# ZYNQ-PS.net
KiCad netlist of a schematic drawn in Altium Designer
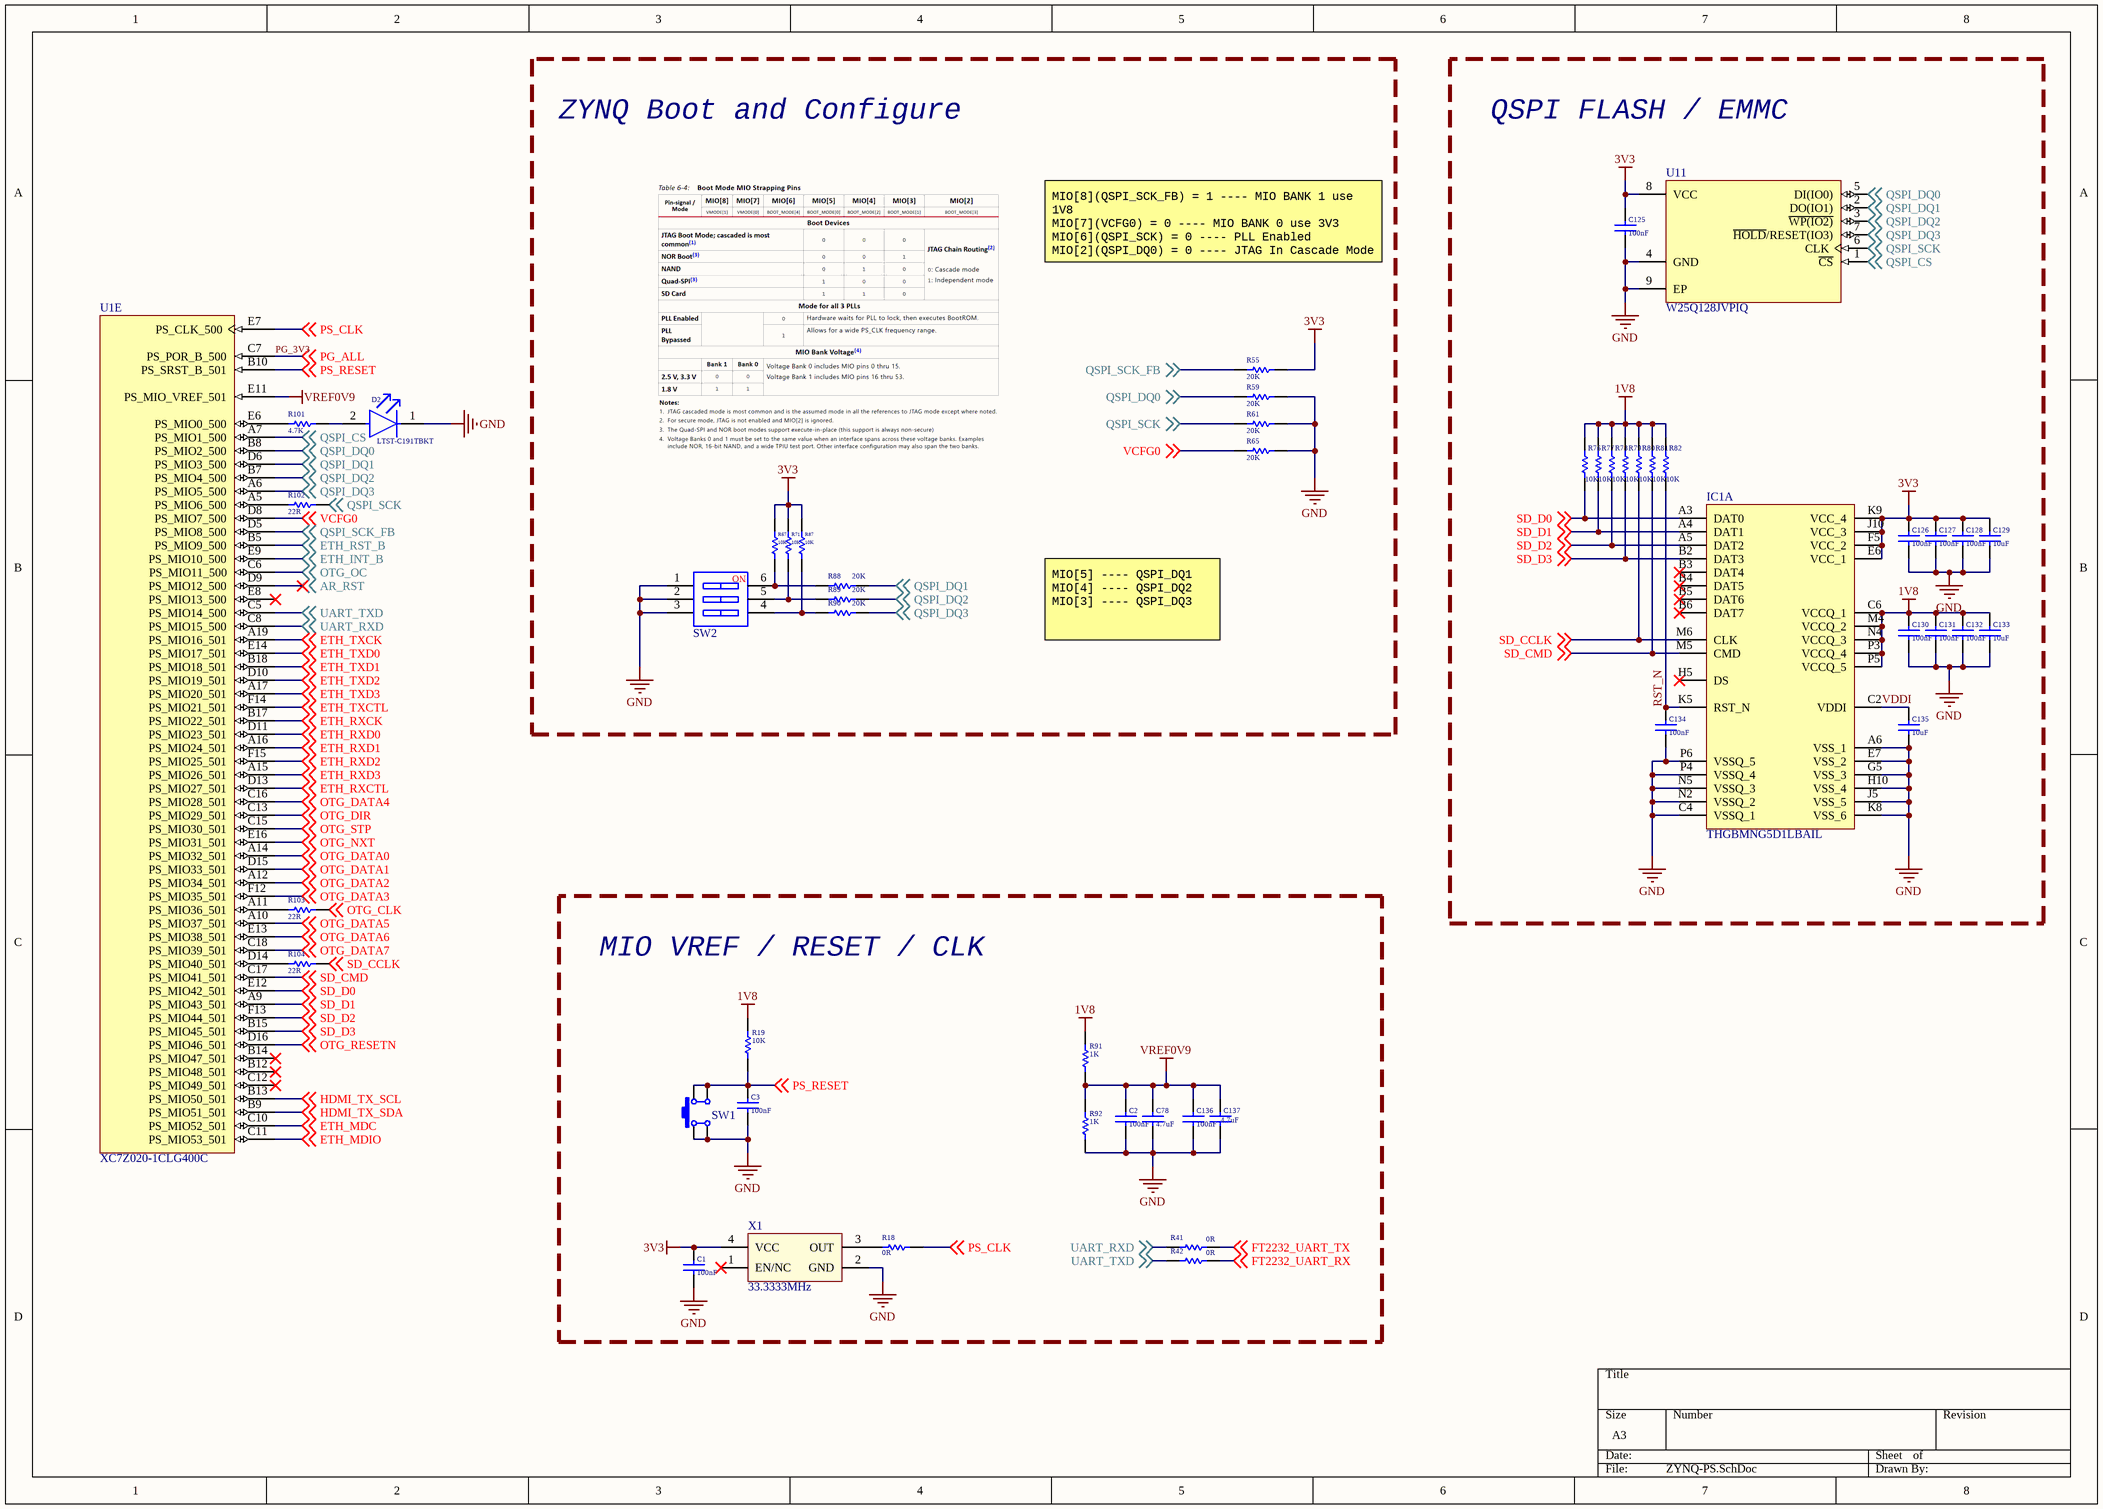
[diagram p0: ZYNQ-PS.SchDoc]

(export (version "E")
  (design (tool "Eeschema 10.0.6"))
  (components
    (comp (ref "C1")
      (value "100nF")
      (footprint "CAPC1005X55X25LL05T10")
      (fields (field (name "PART NUMBER") "GRM155R71H104KE14D") (field (name "MANUFACTURER") "Murata"))
      (libsource (lib "Altium Content Vault") (part "CAP"))
    )
    (comp (ref "C2")
      (value "100nF")
      (footprint "CAPC1005X55X25LL05T10")
      (fields (field (name "PART NUMBER") "GRM155R71H104KE14D") (field (name "MANUFACTURER") "Murata"))
      (libsource (lib "Altium Content Vault") (part "CAP"))
    )
    (comp (ref "C3")
      (value "100nF")
      (footprint "CAPC1005X55X25LL05T10")
      (fields (field (name "PART NUMBER") "GRM155R71H104KE14D") (field (name "MANUFACTURER") "Murata"))
      (libsource (lib "Altium Content Vault") (part "CAP"))
    )
    (comp (ref "C78")
      (value "4.7uF")
      (footprint "CAPC1005X55X25LL05T10")
      (fields (field (name "PART NUMBER") "GRM155R71H104KE14D") (field (name "MANUFACTURER") "Murata"))
      (libsource (lib "Altium Content Vault") (part "CAP"))
    )
    (comp (ref "C125")
      (value "100nF")
      (footprint "CAPC1005X55X25LL05T10")
      (fields (field (name "PART NUMBER") "GRM155R71H104KE14D") (field (name "MANUFACTURER") "Murata"))
      (libsource (lib "Altium Content Vault") (part "CAP"))
    )
    (comp (ref "C126")
      (value "100nF")
      (footprint "CAPC1005X55X25LL05T10")
      (fields (field (name "PART NUMBER") "GRM155R71H104KE14D") (field (name "MANUFACTURER") "Murata"))
      (libsource (lib "Altium Content Vault") (part "CAP"))
    )
    (comp (ref "C127")
      (value "100nF")
      (footprint "CAPC1005X55X25LL05T10")
      (fields (field (name "PART NUMBER") "GRM155R71H104KE14D") (field (name "MANUFACTURER") "Murata"))
      (libsource (lib "Altium Content Vault") (part "CAP"))
    )
    (comp (ref "C128")
      (value "100nF")
      (footprint "CAPC1005X55X25LL05T10")
      (fields (field (name "PART NUMBER") "GRM155R71H104KE14D") (field (name "MANUFACTURER") "Murata"))
      (libsource (lib "Altium Content Vault") (part "CAP"))
    )
    (comp (ref "C129")
      (value "10uF")
      (footprint "CAPC1005X55X25LL05T10")
      (fields (field (name "PART NUMBER") "GRM155R71H104KE14D") (field (name "MANUFACTURER") "Murata"))
      (libsource (lib "Altium Content Vault") (part "CAP"))
    )
    (comp (ref "C130")
      (value "100nF")
      (footprint "CAPC1005X55X25LL05T10")
      (fields (field (name "PART NUMBER") "GRM155R71H104KE14D") (field (name "MANUFACTURER") "Murata"))
      (libsource (lib "Altium Content Vault") (part "CAP"))
    )
    (comp (ref "C131")
      (value "100nF")
      (footprint "CAPC1005X55X25LL05T10")
      (fields (field (name "PART NUMBER") "GRM155R71H104KE14D") (field (name "MANUFACTURER") "Murata"))
      (libsource (lib "Altium Content Vault") (part "CAP"))
    )
    (comp (ref "C132")
      (value "100nF")
      (footprint "CAPC1005X55X25LL05T10")
      (fields (field (name "PART NUMBER") "GRM155R71H104KE14D") (field (name "MANUFACTURER") "Murata"))
      (libsource (lib "Altium Content Vault") (part "CAP"))
    )
    (comp (ref "C133")
      (value "10uF")
      (footprint "CAPC1005X55X25LL05T10")
      (fields (field (name "PART NUMBER") "GRM155R71H104KE14D") (field (name "MANUFACTURER") "Murata"))
      (libsource (lib "Altium Content Vault") (part "CAP"))
    )
    (comp (ref "C134")
      (value "100nF")
      (footprint "CAPC1005X55X25LL05T10")
      (fields (field (name "PART NUMBER") "GRM155R71H104KE14D") (field (name "MANUFACTURER") "Murata"))
      (libsource (lib "Altium Content Vault") (part "CAP"))
    )
    (comp (ref "C135")
      (value "10uF")
      (footprint "CAPC1005X55X25LL05T10")
      (fields (field (name "PART NUMBER") "GRM155R71H104KE14D") (field (name "MANUFACTURER") "Murata"))
      (libsource (lib "Altium Content Vault") (part "CAP"))
    )
    (comp (ref "C136")
      (value "100nF")
      (footprint "CAPC1005X55X25LL05T10")
      (fields (field (name "PART NUMBER") "GRM155R71H104KE14D") (field (name "MANUFACTURER") "Murata"))
      (libsource (lib "Altium Content Vault") (part "CAP"))
    )
    (comp (ref "C137")
      (value "4.7uF")
      (footprint "CAPC1005X55X25LL05T10")
      (fields (field (name "PART NUMBER") "GRM155R71H104KE14D") (field (name "MANUFACTURER") "Murata"))
      (libsource (lib "Altium Content Vault") (part "CAP"))
    )
    (comp (ref "D2")
      (value "LTST-C191TBKT")
      (footprint "FP-LTST-C191TBKT-MFG")
      (description "LED BLUE CLEAR CHIP SMD")
      (libsource (lib "Altium Content Vault") (part "8706943c75ba83719d021d2fdc84c58"))
    )
    (comp (ref "IC1")
      (value "THGBMNG5D1LBAIL")
      (footprint "SamacSys:BGA153C50P14X14_1150X1300X80")
      (description "Integrated Circuit")
      (libsource (lib "SamacSys") (part "THGBMNG5D1LBAIL"))
    )
    (comp (ref "R18")
      (value "0R")
      (footprint "RESC1005X40X25LL05T05")
      (fields (field (name "MANUFACTURER") "Panasonic") (field (name "PART NUMBER") "ERJ-2RKF40R2X"))
      (libsource (lib "Altium Content Vault") (part "RES"))
    )
    (comp (ref "R19")
      (value "10K")
      (footprint "RESC1005X40X25LL05T05")
      (fields (field (name "MANUFACTURER") "Panasonic") (field (name "PART NUMBER") "ERJ-2RKF40R2X"))
      (libsource (lib "Altium Content Vault") (part "RES"))
    )
    (comp (ref "R41")
      (value "0R")
      (footprint "RESC1005X40X25LL05T05")
      (fields (field (name "MANUFACTURER") "Panasonic") (field (name "PART NUMBER") "ERJ-2RKF40R2X"))
      (libsource (lib "Altium Content Vault") (part "RES"))
    )
    (comp (ref "R42")
      (value "0R")
      (footprint "RESC1005X40X25LL05T05")
      (fields (field (name "MANUFACTURER") "Panasonic") (field (name "PART NUMBER") "ERJ-2RKF40R2X"))
      (libsource (lib "Altium Content Vault") (part "RES"))
    )
    (comp (ref "R55")
      (value "20K")
      (footprint "RESC1005X40X25LL05T05")
      (fields (field (name "MANUFACTURER") "Panasonic") (field (name "PART NUMBER") "ERJ-2RKF40R2X"))
      (libsource (lib "Altium Content Vault") (part "RES"))
    )
    (comp (ref "R59")
      (value "20K")
      (footprint "RESC1005X40X25LL05T05")
      (fields (field (name "MANUFACTURER") "Panasonic") (field (name "PART NUMBER") "ERJ-2RKF40R2X"))
      (libsource (lib "Altium Content Vault") (part "RES"))
    )
    (comp (ref "R61")
      (value "20K")
      (footprint "RESC1005X40X25LL05T05")
      (fields (field (name "MANUFACTURER") "Panasonic") (field (name "PART NUMBER") "ERJ-2RKF40R2X"))
      (libsource (lib "Altium Content Vault") (part "RES"))
    )
    (comp (ref "R65")
      (value "20K")
      (footprint "RESC1005X40X25LL05T05")
      (fields (field (name "MANUFACTURER") "Panasonic") (field (name "PART NUMBER") "ERJ-2RKF40R2X"))
      (libsource (lib "Altium Content Vault") (part "RES"))
    )
    (comp (ref "R67")
      (value "10K")
      (footprint "RESC1005X40X25LL05T05")
      (fields (field (name "MANUFACTURER") "Panasonic") (field (name "PART NUMBER") "ERJ-2RKF40R2X"))
      (libsource (lib "Altium Content Vault") (part "RES"))
    )
    (comp (ref "R71")
      (value "10K")
      (footprint "RESC1005X40X25LL05T05")
      (fields (field (name "MANUFACTURER") "Panasonic") (field (name "PART NUMBER") "ERJ-2RKF40R2X"))
      (libsource (lib "Altium Content Vault") (part "RES"))
    )
    (comp (ref "R76")
      (value "10K")
      (footprint "RESC1005X40X25LL05T05")
      (fields (field (name "MANUFACTURER") "Panasonic") (field (name "PART NUMBER") "ERJ-2RKF40R2X"))
      (libsource (lib "Altium Content Vault") (part "RES"))
    )
    (comp (ref "R77")
      (value "10K")
      (footprint "RESC1005X40X25LL05T05")
      (fields (field (name "MANUFACTURER") "Panasonic") (field (name "PART NUMBER") "ERJ-2RKF40R2X"))
      (libsource (lib "Altium Content Vault") (part "RES"))
    )
    (comp (ref "R78")
      (value "10K")
      (footprint "RESC1005X40X25LL05T05")
      (fields (field (name "MANUFACTURER") "Panasonic") (field (name "PART NUMBER") "ERJ-2RKF40R2X"))
      (libsource (lib "Altium Content Vault") (part "RES"))
    )
    (comp (ref "R79")
      (value "10K")
      (footprint "RESC1005X40X25LL05T05")
      (fields (field (name "MANUFACTURER") "Panasonic") (field (name "PART NUMBER") "ERJ-2RKF40R2X"))
      (libsource (lib "Altium Content Vault") (part "RES"))
    )
    (comp (ref "R80")
      (value "10K")
      (footprint "RESC1005X40X25LL05T05")
      (fields (field (name "MANUFACTURER") "Panasonic") (field (name "PART NUMBER") "ERJ-2RKF40R2X"))
      (libsource (lib "Altium Content Vault") (part "RES"))
    )
    (comp (ref "R81")
      (value "10K")
      (footprint "RESC1005X40X25LL05T05")
      (fields (field (name "MANUFACTURER") "Panasonic") (field (name "PART NUMBER") "ERJ-2RKF40R2X"))
      (libsource (lib "Altium Content Vault") (part "RES"))
    )
    (comp (ref "R82")
      (value "10K")
      (footprint "RESC1005X40X25LL05T05")
      (fields (field (name "MANUFACTURER") "Panasonic") (field (name "PART NUMBER") "ERJ-2RKF40R2X"))
      (libsource (lib "Altium Content Vault") (part "RES"))
    )
    (comp (ref "R87")
      (value "10K")
      (footprint "RESC1005X40X25LL05T05")
      (fields (field (name "MANUFACTURER") "Panasonic") (field (name "PART NUMBER") "ERJ-2RKF40R2X"))
      (libsource (lib "Altium Content Vault") (part "RES"))
    )
    (comp (ref "R88")
      (value "20K")
      (footprint "RESC1005X40X25LL05T05")
      (fields (field (name "MANUFACTURER") "Panasonic") (field (name "PART NUMBER") "ERJ-2RKF40R2X"))
      (libsource (lib "Altium Content Vault") (part "RES"))
    )
    (comp (ref "R89")
      (value "20K")
      (footprint "RESC1005X40X25LL05T05")
      (fields (field (name "MANUFACTURER") "Panasonic") (field (name "PART NUMBER") "ERJ-2RKF40R2X"))
      (libsource (lib "Altium Content Vault") (part "RES"))
    )
    (comp (ref "R90")
      (value "20K")
      (footprint "RESC1005X40X25LL05T05")
      (fields (field (name "MANUFACTURER") "Panasonic") (field (name "PART NUMBER") "ERJ-2RKF40R2X"))
      (libsource (lib "Altium Content Vault") (part "RES"))
    )
    (comp (ref "R91")
      (value "1K")
      (footprint "RESC1005X40X25LL05T05")
      (fields (field (name "MANUFACTURER") "Panasonic") (field (name "PART NUMBER") "ERJ-2RKF40R2X"))
      (libsource (lib "Altium Content Vault") (part "RES"))
    )
    (comp (ref "R92")
      (value "1K")
      (footprint "RESC1005X40X25LL05T05")
      (fields (field (name "MANUFACTURER") "Panasonic") (field (name "PART NUMBER") "ERJ-2RKF40R2X"))
      (libsource (lib "Altium Content Vault") (part "RES"))
    )
    (comp (ref "R101")
      (value "4.7K")
      (footprint "RESC1005X40X25LL05T05")
      (fields (field (name "MANUFACTURER") "Panasonic") (field (name "PART NUMBER") "ERJ-2RKF40R2X"))
      (libsource (lib "Altium Content Vault") (part "RES"))
    )
    (comp (ref "R102")
      (value "22R")
      (footprint "RESC1005X40X25LL05T05")
      (fields (field (name "MANUFACTURER") "Panasonic") (field (name "PART NUMBER") "ERJ-2RKF40R2X"))
      (libsource (lib "Altium Content Vault") (part "RES"))
    )
    (comp (ref "R103")
      (value "22R")
      (footprint "RESC1005X40X25LL05T05")
      (fields (field (name "MANUFACTURER") "Panasonic") (field (name "PART NUMBER") "ERJ-2RKF40R2X"))
      (libsource (lib "Altium Content Vault") (part "RES"))
    )
    (comp (ref "R104")
      (value "22R")
      (footprint "RESC1005X40X25LL05T05")
      (fields (field (name "MANUFACTURER") "Panasonic") (field (name "PART NUMBER") "ERJ-2RKF40R2X"))
      (libsource (lib "Altium Content Vault") (part "RES"))
    )
    (comp (ref "SW1")
      (value "3*4*2.5")
      (footprint "SW-SMD-4.2x3.2_4P")
      (description "贴片4脚轻触开关")
      (libsource (lib "0.5 - 按键_开关_蜂鸣器_电池_测试点_Mark点_铜柱") (part "SW SMD-3*4*2.5"))
    )
    (comp (ref "SW2")
      (value "DIP-SW-3P")
      (footprint "SW1.27 SMD-3P")
      (description "3路拨码开关")
      (libsource (lib "0.5 - 按键_开关_蜂鸣器_电池_测试点_Mark点_铜柱") (part "DIP-SW-3P"))
    )
    (comp (ref "U1")
      (value "XC7Z020-1CLG400C")
      (footprint "CLG400")
      (fields (field (name "GENERIC PART NUMBER") "XC7Z020"))
      (libsource (lib "Altium Content Vault") (part "XNLX-XC7Z020-CLG400"))
    )
    (comp (ref "U11")
      (value "W25Q128JVPIQ")
      (footprint "FP-ZP-IPC_C")
      (libsource (lib "HainanU-RoboMaster-硬件组") (part "W25Q128JVPIQ"))
    )
    (comp (ref "X1")
      (value "33.3333MHz")
      (footprint "OSC-2025-4P")
      (description "4脚有源晶振(振荡器)")
      (libsource (lib "0.1 - 电阻-电容-电感-保险丝-晶振-晶体-磁珠-电位器-法拉电容-馈通电容") (part "XTAL-ACT-4P"))
    )
  )
  (nets
    (net (code "1") (name "/RST_N") (class "Default")
      (node (ref "C134") (pin "2") (pinfunction "2_2") (pintype "passive"))
      (node (ref "IC1") (pin "K5") (pinfunction "RST_N_K5") (pintype "passive"))
      (node (ref "R82") (pin "1") (pinfunction "1_1") (pintype "passive"))
    )
    (net (code "2") (name "/VDDI") (class "Default")
      (node (ref "C135") (pin "2") (pinfunction "2_2") (pintype "passive"))
      (node (ref "IC1") (pin "C2") (pinfunction "VDDI_C2") (pintype "passive"))
    )
    (net (code "3") (name "1V8") (class "Default")
      (node (ref "C130") (pin "2") (pinfunction "2_2") (pintype "passive"))
      (node (ref "C131") (pin "2") (pinfunction "2_2") (pintype "passive"))
      (node (ref "C132") (pin "2") (pinfunction "2_2") (pintype "passive"))
      (node (ref "C133") (pin "2") (pinfunction "2_2") (pintype "passive"))
      (node (ref "IC1") (pin "C6") (pinfunction "VCCQ_1_C6") (pintype "passive"))
      (node (ref "IC1") (pin "M4") (pinfunction "VCCQ_2_M4") (pintype "passive"))
      (node (ref "IC1") (pin "N4") (pinfunction "VCCQ_3_N4") (pintype "passive"))
      (node (ref "IC1") (pin "P3") (pinfunction "VCCQ_4_P3") (pintype "passive"))
      (node (ref "IC1") (pin "P5") (pinfunction "VCCQ_5_P5") (pintype "passive"))
      (node (ref "R19") (pin "2") (pinfunction "2_2") (pintype "passive"))
      (node (ref "R76") (pin "2") (pinfunction "2_2") (pintype "passive"))
      (node (ref "R77") (pin "2") (pinfunction "2_2") (pintype "passive"))
      (node (ref "R78") (pin "2") (pinfunction "2_2") (pintype "passive"))
      (node (ref "R79") (pin "2") (pinfunction "2_2") (pintype "passive"))
      (node (ref "R80") (pin "2") (pinfunction "2_2") (pintype "passive"))
      (node (ref "R81") (pin "2") (pinfunction "2_2") (pintype "passive"))
      (node (ref "R82") (pin "2") (pinfunction "2_2") (pintype "passive"))
      (node (ref "R91") (pin "2") (pinfunction "2_2") (pintype "passive"))
    )
    (net (code "4") (name "3V3") (class "Default")
      (node (ref "C1") (pin "2") (pinfunction "2_2") (pintype "passive"))
      (node (ref "C125") (pin "2") (pinfunction "2_2") (pintype "passive"))
      (node (ref "C126") (pin "2") (pinfunction "2_2") (pintype "passive"))
      (node (ref "C127") (pin "2") (pinfunction "2_2") (pintype "passive"))
      (node (ref "C128") (pin "2") (pinfunction "2_2") (pintype "passive"))
      (node (ref "C129") (pin "2") (pinfunction "2_2") (pintype "passive"))
      (node (ref "IC1") (pin "E6") (pinfunction "VCC_1_E6") (pintype "passive"))
      (node (ref "IC1") (pin "F5") (pinfunction "VCC_2_F5") (pintype "passive"))
      (node (ref "IC1") (pin "J10") (pinfunction "VCC_3_J10") (pintype "passive"))
      (node (ref "IC1") (pin "K9") (pinfunction "VCC_4_K9") (pintype "passive"))
      (node (ref "R55") (pin "1") (pinfunction "1_1") (pintype "passive"))
      (node (ref "R67") (pin "1") (pinfunction "1_1") (pintype "passive"))
      (node (ref "R71") (pin "1") (pinfunction "1_1") (pintype "passive"))
      (node (ref "R87") (pin "1") (pinfunction "1_1") (pintype "passive"))
      (node (ref "U11") (pin "8") (pinfunction "VCC_8") (pintype "power_in"))
      (node (ref "X1") (pin "4") (pinfunction "VCC_4") (pintype "passive"))
    )
    (net (code "5") (name "AR_RST") (class "Default")
      (node (ref "U1") (pin "D9") (pinfunction "PS_MIO12_500_D9") (pintype "bidirectional"))
    )
    (net (code "6") (name "ETH_INT_B") (class "Default")
      (node (ref "U1") (pin "E9") (pinfunction "PS_MIO10_500_E9") (pintype "bidirectional"))
    )
    (net (code "7") (name "ETH_MDC") (class "Default")
      (node (ref "U1") (pin "C10") (pinfunction "PS_MIO52_501_C10") (pintype "bidirectional"))
    )
    (net (code "8") (name "ETH_MDIO") (class "Default")
      (node (ref "U1") (pin "C11") (pinfunction "PS_MIO53_501_C11") (pintype "bidirectional"))
    )
    (net (code "9") (name "ETH_RST_B") (class "Default")
      (node (ref "U1") (pin "B5") (pinfunction "PS_MIO9_500_B5") (pintype "bidirectional"))
    )
    (net (code "10") (name "ETH_RXCK") (class "Default")
      (node (ref "U1") (pin "B17") (pinfunction "PS_MIO22_501_B17") (pintype "bidirectional"))
    )
    (net (code "11") (name "ETH_RXCTL") (class "Default")
      (node (ref "U1") (pin "D13") (pinfunction "PS_MIO27_501_D13") (pintype "bidirectional"))
    )
    (net (code "12") (name "ETH_RXD0") (class "Default")
      (node (ref "U1") (pin "D11") (pinfunction "PS_MIO23_501_D11") (pintype "bidirectional"))
    )
    (net (code "13") (name "ETH_RXD1") (class "Default")
      (node (ref "U1") (pin "A16") (pinfunction "PS_MIO24_501_A16") (pintype "bidirectional"))
    )
    (net (code "14") (name "ETH_RXD2") (class "Default")
      (node (ref "U1") (pin "F15") (pinfunction "PS_MIO25_501_F15") (pintype "bidirectional"))
    )
    (net (code "15") (name "ETH_RXD3") (class "Default")
      (node (ref "U1") (pin "A15") (pinfunction "PS_MIO26_501_A15") (pintype "bidirectional"))
    )
    (net (code "16") (name "ETH_TXCK") (class "Default")
      (node (ref "U1") (pin "A19") (pinfunction "PS_MIO16_501_A19") (pintype "bidirectional"))
    )
    (net (code "17") (name "ETH_TXCTL") (class "Default")
      (node (ref "U1") (pin "F14") (pinfunction "PS_MIO21_501_F14") (pintype "bidirectional"))
    )
    (net (code "18") (name "ETH_TXD0") (class "Default")
      (node (ref "U1") (pin "E14") (pinfunction "PS_MIO17_501_E14") (pintype "bidirectional"))
    )
    (net (code "19") (name "ETH_TXD1") (class "Default")
      (node (ref "U1") (pin "B18") (pinfunction "PS_MIO18_501_B18") (pintype "bidirectional"))
    )
    (net (code "20") (name "ETH_TXD2") (class "Default")
      (node (ref "U1") (pin "D10") (pinfunction "PS_MIO19_501_D10") (pintype "bidirectional"))
    )
    (net (code "21") (name "ETH_TXD3") (class "Default")
      (node (ref "U1") (pin "A17") (pinfunction "PS_MIO20_501_A17") (pintype "bidirectional"))
    )
    (net (code "22") (name "FT2232_UART_RX") (class "Default")
      (node (ref "R42") (pin "1") (pinfunction "1_1") (pintype "passive"))
    )
    (net (code "23") (name "FT2232_UART_TX") (class "Default")
      (node (ref "R41") (pin "1") (pinfunction "1_1") (pintype "passive"))
    )
    (net (code "24") (name "GND") (class "Default")
      (node (ref "C1") (pin "1") (pinfunction "1_1") (pintype "passive"))
      (node (ref "C125") (pin "1") (pinfunction "1_1") (pintype "passive"))
      (node (ref "C126") (pin "1") (pinfunction "1_1") (pintype "passive"))
      (node (ref "C127") (pin "1") (pinfunction "1_1") (pintype "passive"))
      (node (ref "C128") (pin "1") (pinfunction "1_1") (pintype "passive"))
      (node (ref "C129") (pin "1") (pinfunction "1_1") (pintype "passive"))
      (node (ref "C130") (pin "1") (pinfunction "1_1") (pintype "passive"))
      (node (ref "C131") (pin "1") (pinfunction "1_1") (pintype "passive"))
      (node (ref "C132") (pin "1") (pinfunction "1_1") (pintype "passive"))
      (node (ref "C133") (pin "1") (pinfunction "1_1") (pintype "passive"))
      (node (ref "C134") (pin "1") (pinfunction "1_1") (pintype "passive"))
      (node (ref "C135") (pin "1") (pinfunction "1_1") (pintype "passive"))
      (node (ref "C136") (pin "1") (pinfunction "1_1") (pintype "passive"))
      (node (ref "C137") (pin "1") (pinfunction "1_1") (pintype "passive"))
      (node (ref "C2") (pin "1") (pinfunction "1_1") (pintype "passive"))
      (node (ref "C3") (pin "1") (pinfunction "1_1") (pintype "passive"))
      (node (ref "C78") (pin "1") (pinfunction "1_1") (pintype "passive"))
      (node (ref "D2") (pin "1") (pinfunction "C_1") (pintype "passive"))
      (node (ref "IC1") (pin "A6") (pinfunction "VSS_1_A6") (pintype "passive"))
      (node (ref "IC1") (pin "C4") (pinfunction "VSSQ_1_C4") (pintype "passive"))
      (node (ref "IC1") (pin "E7") (pinfunction "VSS_2_E7") (pintype "passive"))
      (node (ref "IC1") (pin "G5") (pinfunction "VSS_3_G5") (pintype "passive"))
      (node (ref "IC1") (pin "H10") (pinfunction "VSS_4_H10") (pintype "passive"))
      (node (ref "IC1") (pin "J5") (pinfunction "VSS_5_J5") (pintype "passive"))
      (node (ref "IC1") (pin "K8") (pinfunction "VSS_6_K8") (pintype "passive"))
      (node (ref "IC1") (pin "N2") (pinfunction "VSSQ_2_N2") (pintype "passive"))
      (node (ref "IC1") (pin "N5") (pinfunction "VSSQ_3_N5") (pintype "passive"))
      (node (ref "IC1") (pin "P4") (pinfunction "VSSQ_4_P4") (pintype "passive"))
      (node (ref "IC1") (pin "P6") (pinfunction "VSSQ_5_P6") (pintype "passive"))
      (node (ref "R59") (pin "1") (pinfunction "1_1") (pintype "passive"))
      (node (ref "R61") (pin "1") (pinfunction "1_1") (pintype "passive"))
      (node (ref "R65") (pin "1") (pinfunction "1_1") (pintype "passive"))
      (node (ref "R92") (pin "1") (pinfunction "1_1") (pintype "passive"))
      (node (ref "SW1") (pin "1") (pinfunction "1_1") (pintype "passive"))
      (node (ref "SW1") (pin "4") (pinfunction "4_4") (pintype "passive"))
      (node (ref "SW2") (pin "1") (pinfunction "1_1") (pintype "passive"))
      (node (ref "SW2") (pin "2") (pinfunction "2_2") (pintype "passive"))
      (node (ref "SW2") (pin "3") (pinfunction "3_3") (pintype "passive"))
      (node (ref "U11") (pin "4") (pinfunction "GND_4") (pintype "power_in"))
      (node (ref "U11") (pin "9") (pinfunction "EP_9") (pintype "power_in"))
      (node (ref "X1") (pin "2") (pinfunction "GND_2") (pintype "passive"))
    )
    (net (code "25") (name "HDMI_TX_SCL") (class "Default")
      (node (ref "U1") (pin "B13") (pinfunction "PS_MIO50_501_B13") (pintype "bidirectional"))
    )
    (net (code "26") (name "HDMI_TX_SDA") (class "Default")
      (node (ref "U1") (pin "B9") (pinfunction "PS_MIO51_501_B9") (pintype "bidirectional"))
    )
    (net (code "27") (name "Net-(D2-A)") (class "Default")
      (node (ref "D2") (pin "2") (pinfunction "A_2") (pintype "passive"))
      (node (ref "R101") (pin "1") (pinfunction "1_1") (pintype "passive"))
    )
    (net (code "28") (name "Net-(R67-Pad2)") (class "Default")
      (node (ref "R67") (pin "2") (pinfunction "2_2") (pintype "passive"))
      (node (ref "R88") (pin "2") (pinfunction "2_2") (pintype "passive"))
      (node (ref "SW2") (pin "6") (pinfunction "6_6") (pintype "passive"))
    )
    (net (code "29") (name "Net-(R71-Pad2)") (class "Default")
      (node (ref "R71") (pin "2") (pinfunction "2_2") (pintype "passive"))
      (node (ref "R89") (pin "2") (pinfunction "2_2") (pintype "passive"))
      (node (ref "SW2") (pin "5") (pinfunction "5_5") (pintype "passive"))
    )
    (net (code "30") (name "Net-(R87-Pad2)") (class "Default")
      (node (ref "R87") (pin "2") (pinfunction "2_2") (pintype "passive"))
      (node (ref "R90") (pin "2") (pinfunction "2_2") (pintype "passive"))
      (node (ref "SW2") (pin "4") (pinfunction "4_4") (pintype "passive"))
    )
    (net (code "31") (name "Net-(U1E-PS_MIO0_500)") (class "Default")
      (node (ref "R101") (pin "2") (pinfunction "2_2") (pintype "passive"))
      (node (ref "U1") (pin "E6") (pinfunction "PS_MIO0_500_E6") (pintype "bidirectional"))
    )
    (net (code "32") (name "Net-(U1E-PS_MIO6_500)") (class "Default")
      (node (ref "R102") (pin "2") (pinfunction "2_2") (pintype "passive"))
      (node (ref "U1") (pin "A5") (pinfunction "PS_MIO6_500_A5") (pintype "bidirectional"))
    )
    (net (code "33") (name "Net-(U1E-PS_MIO36_501)") (class "Default")
      (node (ref "R103") (pin "2") (pinfunction "2_2") (pintype "passive"))
      (node (ref "U1") (pin "A11") (pinfunction "PS_MIO36_501_A11") (pintype "bidirectional"))
    )
    (net (code "34") (name "Net-(U1E-PS_MIO40_501)") (class "Default")
      (node (ref "R104") (pin "2") (pinfunction "2_2") (pintype "passive"))
      (node (ref "U1") (pin "D14") (pinfunction "PS_MIO40_501_D14") (pintype "bidirectional"))
    )
    (net (code "35") (name "Net-(X1-OUT)") (class "Default")
      (node (ref "R18") (pin "1") (pinfunction "1_1") (pintype "passive"))
      (node (ref "X1") (pin "3") (pinfunction "OUT_3") (pintype "passive"))
    )
    (net (code "36") (name "OTG_CLK") (class "Default")
      (node (ref "R103") (pin "1") (pinfunction "1_1") (pintype "passive"))
    )
    (net (code "37") (name "OTG_DATA0") (class "Default")
      (node (ref "U1") (pin "A14") (pinfunction "PS_MIO32_501_A14") (pintype "bidirectional"))
    )
    (net (code "38") (name "OTG_DATA1") (class "Default")
      (node (ref "U1") (pin "D15") (pinfunction "PS_MIO33_501_D15") (pintype "bidirectional"))
    )
    (net (code "39") (name "OTG_DATA2") (class "Default")
      (node (ref "U1") (pin "A12") (pinfunction "PS_MIO34_501_A12") (pintype "bidirectional"))
    )
    (net (code "40") (name "OTG_DATA3") (class "Default")
      (node (ref "U1") (pin "F12") (pinfunction "PS_MIO35_501_F12") (pintype "bidirectional"))
    )
    (net (code "41") (name "OTG_DATA4") (class "Default")
      (node (ref "U1") (pin "C16") (pinfunction "PS_MIO28_501_C16") (pintype "bidirectional"))
    )
    (net (code "42") (name "OTG_DATA5") (class "Default")
      (node (ref "U1") (pin "A10") (pinfunction "PS_MIO37_501_A10") (pintype "bidirectional"))
    )
    (net (code "43") (name "OTG_DATA6") (class "Default")
      (node (ref "U1") (pin "E13") (pinfunction "PS_MIO38_501_E13") (pintype "bidirectional"))
    )
    (net (code "44") (name "OTG_DATA7") (class "Default")
      (node (ref "U1") (pin "C18") (pinfunction "PS_MIO39_501_C18") (pintype "bidirectional"))
    )
    (net (code "45") (name "OTG_DIR") (class "Default")
      (node (ref "U1") (pin "C13") (pinfunction "PS_MIO29_501_C13") (pintype "bidirectional"))
    )
    (net (code "46") (name "OTG_NXT") (class "Default")
      (node (ref "U1") (pin "E16") (pinfunction "PS_MIO31_501_E16") (pintype "bidirectional"))
    )
    (net (code "47") (name "OTG_OC") (class "Default")
      (node (ref "U1") (pin "C6") (pinfunction "PS_MIO11_500_C6") (pintype "bidirectional"))
    )
    (net (code "48") (name "OTG_RESETN") (class "Default")
      (node (ref "U1") (pin "D16") (pinfunction "PS_MIO46_501_D16") (pintype "bidirectional"))
    )
    (net (code "49") (name "OTG_STP") (class "Default")
      (node (ref "U1") (pin "C15") (pinfunction "PS_MIO30_501_C15") (pintype "bidirectional"))
    )
    (net (code "50") (name "PG_ALL") (class "Default")
      (node (ref "U1") (pin "C7") (pinfunction "PS_POR_B_500_C7") (pintype "input"))
    )
    (net (code "51") (name "PS_CLK") (class "Default")
      (node (ref "R18") (pin "2") (pinfunction "2_2") (pintype "passive"))
      (node (ref "U1") (pin "E7") (pinfunction "PS_CLK_500_E7") (pintype "input"))
    )
    (net (code "52") (name "PS_RESET") (class "Default")
      (node (ref "C3") (pin "2") (pinfunction "2_2") (pintype "passive"))
      (node (ref "R19") (pin "1") (pinfunction "1_1") (pintype "passive"))
      (node (ref "SW1") (pin "2") (pinfunction "2_2") (pintype "passive"))
      (node (ref "SW1") (pin "3") (pinfunction "3_3") (pintype "passive"))
      (node (ref "U1") (pin "B10") (pinfunction "PS_SRST_B_501_B10") (pintype "input"))
    )
    (net (code "53") (name "QSPI_CS") (class "Default")
      (node (ref "U1") (pin "A7") (pinfunction "PS_MIO1_500_A7") (pintype "bidirectional"))
      (node (ref "U11") (pin "1") (pinfunction "~{CS}_1") (pintype "input"))
    )
    (net (code "54") (name "QSPI_DQ0") (class "Default")
      (node (ref "R59") (pin "2") (pinfunction "2_2") (pintype "passive"))
      (node (ref "U1") (pin "B8") (pinfunction "PS_MIO2_500_B8") (pintype "bidirectional"))
      (node (ref "U11") (pin "5") (pinfunction "DI(IO0)_5") (pintype "bidirectional"))
    )
    (net (code "55") (name "QSPI_DQ1") (class "Default")
      (node (ref "R88") (pin "1") (pinfunction "1_1") (pintype "passive"))
      (node (ref "U1") (pin "D6") (pinfunction "PS_MIO3_500_D6") (pintype "bidirectional"))
      (node (ref "U11") (pin "2") (pinfunction "DO(IO1)_2") (pintype "bidirectional"))
    )
    (net (code "56") (name "QSPI_DQ2") (class "Default")
      (node (ref "R89") (pin "1") (pinfunction "1_1") (pintype "passive"))
      (node (ref "U1") (pin "B7") (pinfunction "PS_MIO4_500_B7") (pintype "bidirectional"))
      (node (ref "U11") (pin "3") (pinfunction "~{WP(IO2)}_3") (pintype "bidirectional"))
    )
    (net (code "57") (name "QSPI_DQ3") (class "Default")
      (node (ref "R90") (pin "1") (pinfunction "1_1") (pintype "passive"))
      (node (ref "U1") (pin "A6") (pinfunction "PS_MIO5_500_A6") (pintype "bidirectional"))
      (node (ref "U11") (pin "7") (pinfunction "~{HOLD}/RESET(IO3)_7") (pintype "bidirectional"))
    )
    (net (code "58") (name "QSPI_SCK") (class "Default")
      (node (ref "R102") (pin "1") (pinfunction "1_1") (pintype "passive"))
      (node (ref "R61") (pin "2") (pinfunction "2_2") (pintype "passive"))
      (node (ref "U11") (pin "6") (pinfunction "CLK_6") (pintype "input"))
    )
    (net (code "59") (name "QSPI_SCK_FB") (class "Default")
      (node (ref "R55") (pin "2") (pinfunction "2_2") (pintype "passive"))
      (node (ref "U1") (pin "D5") (pinfunction "PS_MIO8_500_D5") (pintype "bidirectional"))
    )
    (net (code "60") (name "SD_CCLK") (class "Default")
      (node (ref "IC1") (pin "M6") (pinfunction "CLK_M6") (pintype "passive"))
      (node (ref "R104") (pin "1") (pinfunction "1_1") (pintype "passive"))
      (node (ref "R80") (pin "1") (pinfunction "1_1") (pintype "passive"))
    )
    (net (code "61") (name "SD_CMD") (class "Default")
      (node (ref "IC1") (pin "M5") (pinfunction "CMD_M5") (pintype "passive"))
      (node (ref "R81") (pin "1") (pinfunction "1_1") (pintype "passive"))
      (node (ref "U1") (pin "C17") (pinfunction "PS_MIO41_501_C17") (pintype "bidirectional"))
    )
    (net (code "62") (name "SD_D0") (class "Default")
      (node (ref "IC1") (pin "A3") (pinfunction "DAT0_A3") (pintype "passive"))
      (node (ref "R76") (pin "1") (pinfunction "1_1") (pintype "passive"))
      (node (ref "U1") (pin "E12") (pinfunction "PS_MIO42_501_E12") (pintype "bidirectional"))
    )
    (net (code "63") (name "SD_D1") (class "Default")
      (node (ref "IC1") (pin "A4") (pinfunction "DAT1_A4") (pintype "passive"))
      (node (ref "R77") (pin "1") (pinfunction "1_1") (pintype "passive"))
      (node (ref "U1") (pin "A9") (pinfunction "PS_MIO43_501_A9") (pintype "bidirectional"))
    )
    (net (code "64") (name "SD_D2") (class "Default")
      (node (ref "IC1") (pin "A5") (pinfunction "DAT2_A5") (pintype "passive"))
      (node (ref "R78") (pin "1") (pinfunction "1_1") (pintype "passive"))
      (node (ref "U1") (pin "F13") (pinfunction "PS_MIO44_501_F13") (pintype "bidirectional"))
    )
    (net (code "65") (name "SD_D3") (class "Default")
      (node (ref "IC1") (pin "B2") (pinfunction "DAT3_B2") (pintype "passive"))
      (node (ref "R79") (pin "1") (pinfunction "1_1") (pintype "passive"))
      (node (ref "U1") (pin "B15") (pinfunction "PS_MIO45_501_B15") (pintype "bidirectional"))
    )
    (net (code "66") (name "UART_RXD") (class "Default")
      (node (ref "R41") (pin "2") (pinfunction "2_2") (pintype "passive"))
      (node (ref "U1") (pin "C8") (pinfunction "PS_MIO15_500_C8") (pintype "bidirectional"))
    )
    (net (code "67") (name "UART_TXD") (class "Default")
      (node (ref "R42") (pin "2") (pinfunction "2_2") (pintype "passive"))
      (node (ref "U1") (pin "C5") (pinfunction "PS_MIO14_500_C5") (pintype "bidirectional"))
    )
    (net (code "68") (name "VCFG0") (class "Default")
      (node (ref "R65") (pin "2") (pinfunction "2_2") (pintype "passive"))
      (node (ref "U1") (pin "D8") (pinfunction "PS_MIO7_500_D8") (pintype "bidirectional"))
    )
    (net (code "69") (name "VREF0V9") (class "Default")
      (node (ref "C136") (pin "2") (pinfunction "2_2") (pintype "passive"))
      (node (ref "C137") (pin "2") (pinfunction "2_2") (pintype "passive"))
      (node (ref "C2") (pin "2") (pinfunction "2_2") (pintype "passive"))
      (node (ref "C78") (pin "2") (pinfunction "2_2") (pintype "passive"))
      (node (ref "R91") (pin "1") (pinfunction "1_1") (pintype "passive"))
      (node (ref "R92") (pin "2") (pinfunction "2_2") (pintype "passive"))
      (node (ref "U1") (pin "E11") (pinfunction "PS_MIO_VREF_501_E11") (pintype "input"))
    )
    (net (code "70") (name "unconnected-(IC1A-DAT4-PadB3)") (class "Default")
      (node (ref "IC1") (pin "B3") (pinfunction "DAT4_B3") (pintype "passive+no_connect"))
    )
    (net (code "71") (name "unconnected-(IC1A-DAT5-PadB4)") (class "Default")
      (node (ref "IC1") (pin "B4") (pinfunction "DAT5_B4") (pintype "passive+no_connect"))
    )
    (net (code "72") (name "unconnected-(IC1A-DAT6-PadB5)") (class "Default")
      (node (ref "IC1") (pin "B5") (pinfunction "DAT6_B5") (pintype "passive+no_connect"))
    )
    (net (code "73") (name "unconnected-(IC1A-DAT7-PadB6)") (class "Default")
      (node (ref "IC1") (pin "B6") (pinfunction "DAT7_B6") (pintype "passive+no_connect"))
    )
    (net (code "74") (name "unconnected-(IC1A-DS-PadH5)") (class "Default")
      (node (ref "IC1") (pin "H5") (pinfunction "DS_H5") (pintype "passive+no_connect"))
    )
    (net (code "75") (name "unconnected-(U1E-PS_MIO13_500-PadE8)") (class "Default")
      (node (ref "U1") (pin "E8") (pinfunction "PS_MIO13_500_E8") (pintype "bidirectional+no_connect"))
    )
    (net (code "76") (name "unconnected-(U1E-PS_MIO47_501-PadB14)") (class "Default")
      (node (ref "U1") (pin "B14") (pinfunction "PS_MIO47_501_B14") (pintype "bidirectional+no_connect"))
    )
    (net (code "77") (name "unconnected-(U1E-PS_MIO48_501-PadB12)") (class "Default")
      (node (ref "U1") (pin "B12") (pinfunction "PS_MIO48_501_B12") (pintype "bidirectional+no_connect"))
    )
    (net (code "78") (name "unconnected-(U1E-PS_MIO49_501-PadC12)") (class "Default")
      (node (ref "U1") (pin "C12") (pinfunction "PS_MIO49_501_C12") (pintype "bidirectional+no_connect"))
    )
    (net (code "79") (name "unconnected-(X1-EN{slash}NC-Pad1)") (class "Default")
      (node (ref "X1") (pin "1") (pinfunction "EN/NC_1") (pintype "passive+no_connect"))
    )
  )
)
